# Buffer.net
KiCad netlist of a schematic drawn in Altium Designer
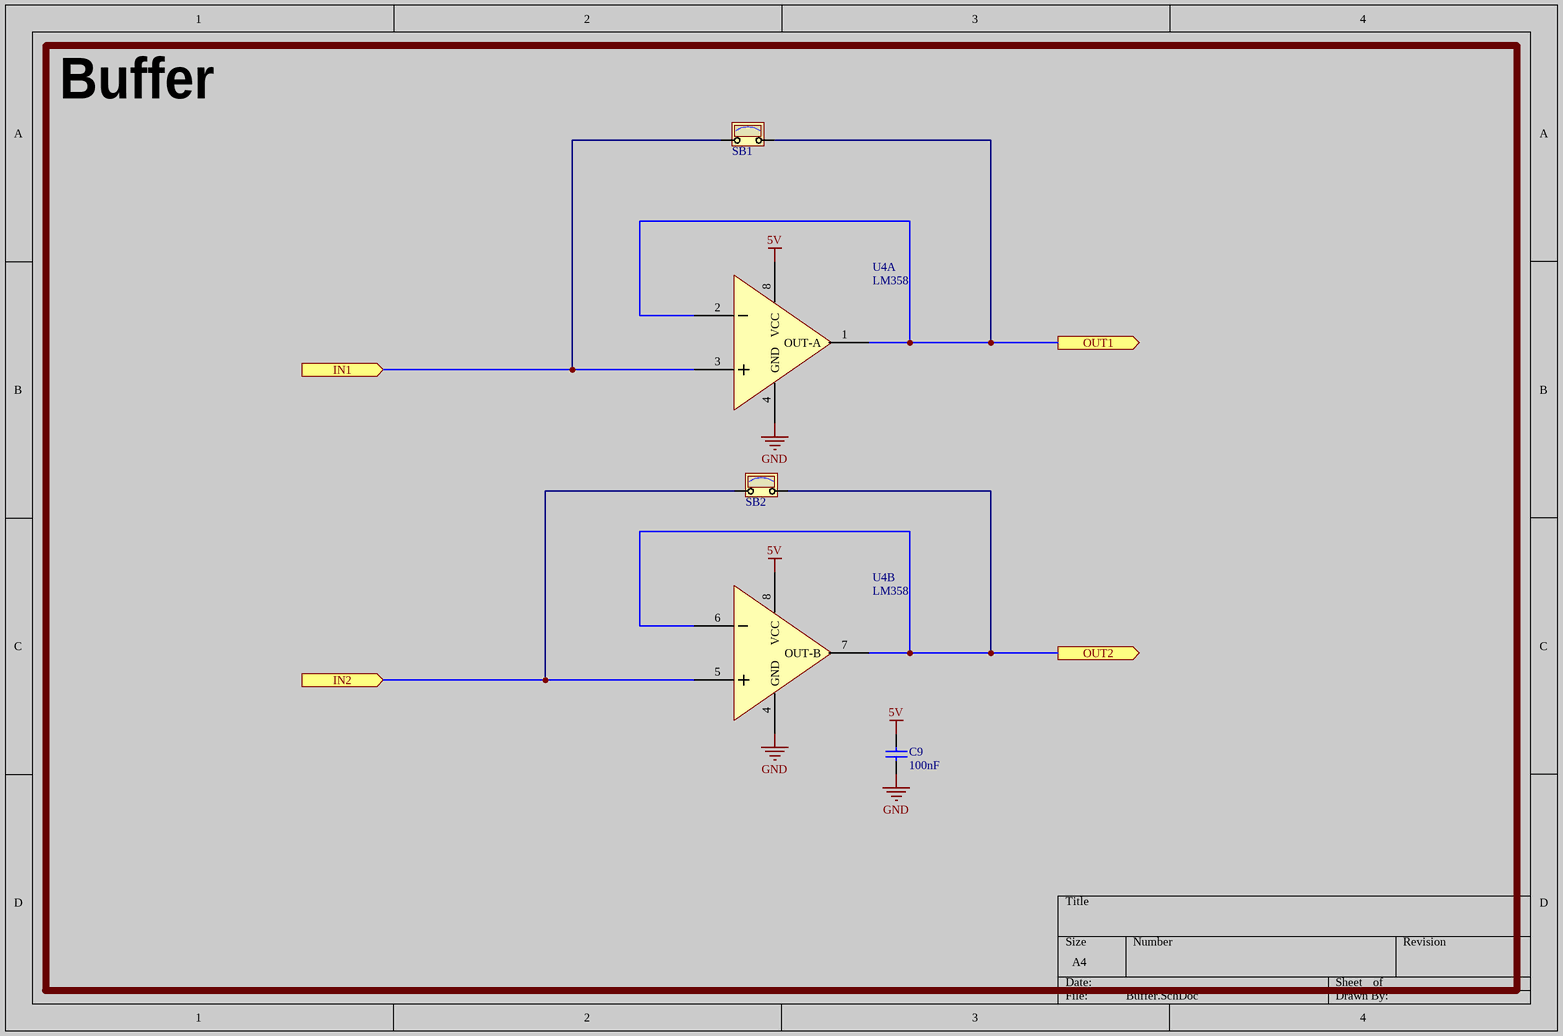
[diagram p0: Buffer.SchDoc]

(export (version "E")
  (design (tool "Eeschema 10.0.6"))
  (components
    (comp (ref "C9")
      (value "100nF")
      (footprint "TaraPcbLib:CAPC0603")
      (description "Capacitor")
      (fields (field (name "PUBLISHER") "Altium Limited"))
      (libsource (lib "TaraSchlib") (part "Cap"))
    )
    (comp (ref "SB1")
      (value "Solder Bridge ON")
      (footprint "LIB:RES 0R")
      (libsource (lib "eLIB") (part "SB_ON"))
    )
    (comp (ref "SB2")
      (value "Solder Bridge ON")
      (footprint "LIB:RES 0R")
      (libsource (lib "eLIB") (part "SB_ON"))
    )
    (comp (ref "U4")
      (value "LM358")
      (footprint "SOP8")
      (description "Single Supply Dual Operational Amplifier")
      (libsource (lib "TaraSchlib") (part "LM358"))
    )
  )
  (nets
    (net (code "1") (name "/IN1") (class "Default")
      (node (ref "SB1") (pin "1") (pinfunction "1_1") (pintype "passive"))
      (node (ref "U4") (pin "3") (pinfunction "-_3") (pintype "passive"))
    )
    (net (code "2") (name "/IN2") (class "Default")
      (node (ref "SB2") (pin "1") (pinfunction "1_1") (pintype "passive"))
      (node (ref "U4") (pin "5") (pinfunction "+_5") (pintype "passive"))
    )
    (net (code "3") (name "/OUT1") (class "Default")
      (node (ref "SB1") (pin "2") (pinfunction "2_2") (pintype "passive"))
      (node (ref "U4") (pin "1") (pinfunction "OUT-A_1") (pintype "passive"))
      (node (ref "U4") (pin "2") (pinfunction "+_2") (pintype "passive"))
    )
    (net (code "4") (name "/OUT2") (class "Default")
      (node (ref "SB2") (pin "2") (pinfunction "2_2") (pintype "passive"))
      (node (ref "U4") (pin "6") (pinfunction "-_6") (pintype "passive"))
      (node (ref "U4") (pin "7") (pinfunction "OUT-B_7") (pintype "passive"))
    )
    (net (code "5") (name "5V") (class "Default")
      (node (ref "C9") (pin "1") (pinfunction "1_1") (pintype "passive"))
      (node (ref "U4") (pin "8") (pinfunction "VCC_8") (pintype "passive"))
    )
    (net (code "6") (name "GND") (class "Default")
      (node (ref "C9") (pin "2") (pinfunction "2_2") (pintype "passive"))
      (node (ref "U4") (pin "4") (pinfunction "GND_4") (pintype "passive"))
    )
  )
)
